# v1_0.net
KiCad netlist of a schematic drawn in Altium Designer
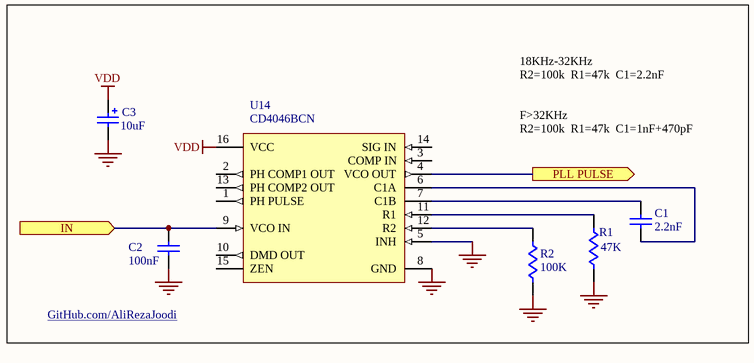
[diagram p0: v1.0.SchDoc]

(export (version "E")
  (design (tool "Eeschema 10.0.6"))
  (components
    (comp (ref "C1")
      (value "2.2nF")
      (footprint "CAPNTO3.18-4.83x2.67")
      (description "Capacitor")
      (fields (field (name "MANUFACTURER") "Generic Components") (field (name "PUBLISHER") "Altium Limited"))
      (libsource (lib "Miscellaneous Devices") (part "Cap"))
    )
    (comp (ref "C2")
      (value "100nF")
      (footprint "CAPNTO5.08-7.37x3.94")
      (description "Capacitor")
      (fields (field (name "MANUFACTURER") "Generic Components") (field (name "PUBLISHER") "Altium Limited"))
      (libsource (lib "Miscellaneous Devices") (part "Cap"))
    )
    (comp (ref "C3")
      (value "10uF")
      (footprint "CAPPR2.5-6.3x5")
      (description "Polarized Capacitor (Radial)")
      (fields (field (name "MANUFACTURER") "Generic Components") (field (name "PUBLISHER") "Altium Limited"))
      (libsource (lib "Miscellaneous Devices") (part "Cap Pol1"))
    )
    (comp (ref "R1")
      (value "47K")
      (footprint "AXIAL-0.4")
      (description "Resistor")
      (fields (field (name "MANUFACTURER") "Generic Components") (field (name "PUBLISHER") "Altium Limited"))
      (libsource (lib "Miscellaneous Devices") (part "Res1"))
    )
    (comp (ref "R2")
      (value "100K")
      (footprint "AXIAL-0.4")
      (description "Resistor")
      (fields (field (name "MANUFACTURER") "Generic Components") (field (name "PUBLISHER") "Altium Limited"))
      (libsource (lib "Miscellaneous Devices") (part "Res1"))
    )
    (comp (ref "U14")
      (value "CD4046BCN")
      (footprint "N16E")
      (description "Micropower Phase-Locked Loop")
      (fields (field (name "Comment") "4046") (field (name "PUBLISHER") "Altium Limited"))
      (libsource (lib "FSC Comm Phase Locked Loop") (part "CD4046BCN"))
    )
  )
  (nets
    (net (code "1") (name "/IN") (class "Default")
      (node (ref "C2") (pin "1") (pinfunction "1_1") (pintype "passive"))
      (node (ref "U14") (pin "9") (pinfunction "VCO_IN_9") (pintype "input"))
    )
    (net (code "2") (name "/PLL PULSE") (class "Default")
      (node (ref "U14") (pin "4") (pinfunction "VCO_OUT_4") (pintype "output"))
    )
    (net (code "3") (name "GND") (class "Default")
      (node (ref "C2") (pin "2") (pinfunction "2_2") (pintype "passive"))
      (node (ref "C3") (pin "2") (pinfunction "2_2") (pintype "passive"))
      (node (ref "R1") (pin "1") (pinfunction "1_1") (pintype "passive"))
      (node (ref "R2") (pin "1") (pinfunction "1_1") (pintype "passive"))
      (node (ref "U14") (pin "5") (pinfunction "INH_5") (pintype "input"))
      (node (ref "U14") (pin "8") (pinfunction "GND_8") (pintype "power_in"))
    )
    (net (code "4") (name "Net-(U14-C1A)") (class "Default")
      (node (ref "C1") (pin "2") (pinfunction "2_2") (pintype "passive"))
      (node (ref "U14") (pin "6") (pinfunction "C1A_6") (pintype "passive"))
    )
    (net (code "5") (name "Net-(U14-C1B)") (class "Default")
      (node (ref "C1") (pin "1") (pinfunction "1_1") (pintype "passive"))
      (node (ref "U14") (pin "7") (pinfunction "C1B_7") (pintype "passive"))
    )
    (net (code "6") (name "Net-(U14-R1)") (class "Default")
      (node (ref "R1") (pin "2") (pinfunction "2_2") (pintype "passive"))
      (node (ref "U14") (pin "11") (pinfunction "R1_11") (pintype "input"))
    )
    (net (code "7") (name "Net-(U14-R2)") (class "Default")
      (node (ref "R2") (pin "2") (pinfunction "2_2") (pintype "passive"))
      (node (ref "U14") (pin "12") (pinfunction "R2_12") (pintype "input"))
    )
    (net (code "8") (name "VDD") (class "Default")
      (node (ref "C3") (pin "1") (pinfunction "1_1") (pintype "passive"))
      (node (ref "U14") (pin "16") (pinfunction "VCC_16") (pintype "power_in"))
    )
    (net (code "9") (name "unconnected-(U14-COMP_IN-Pad3)") (class "Default")
      (node (ref "U14") (pin "3") (pinfunction "COMP_IN_3") (pintype "input"))
    )
    (net (code "10") (name "unconnected-(U14-DMD_OUT-Pad10)") (class "Default")
      (node (ref "U14") (pin "10") (pinfunction "DMD_OUT_10") (pintype "output"))
    )
    (net (code "11") (name "unconnected-(U14-PH_COMP1_OUT-Pad2)") (class "Default")
      (node (ref "U14") (pin "2") (pinfunction "PH_COMP1_OUT_2") (pintype "output"))
    )
    (net (code "12") (name "unconnected-(U14-PH_COMP2_OUT-Pad13)") (class "Default")
      (node (ref "U14") (pin "13") (pinfunction "PH_COMP2_OUT_13") (pintype "output"))
    )
    (net (code "13") (name "unconnected-(U14-PH_PULSE-Pad1)") (class "Default")
      (node (ref "U14") (pin "1") (pinfunction "PH_PULSE_1") (pintype "output"))
    )
    (net (code "14") (name "unconnected-(U14-SIG_IN-Pad14)") (class "Default")
      (node (ref "U14") (pin "14") (pinfunction "SIG_IN_14") (pintype "input"))
    )
    (net (code "15") (name "unconnected-(U14-ZEN-Pad15)") (class "Default")
      (node (ref "U14") (pin "15") (pinfunction "ZEN_15") (pintype "passive"))
    )
  )
)
